# picoslidertoy.net
KiCad netlist of a schematic drawn in EAGLE
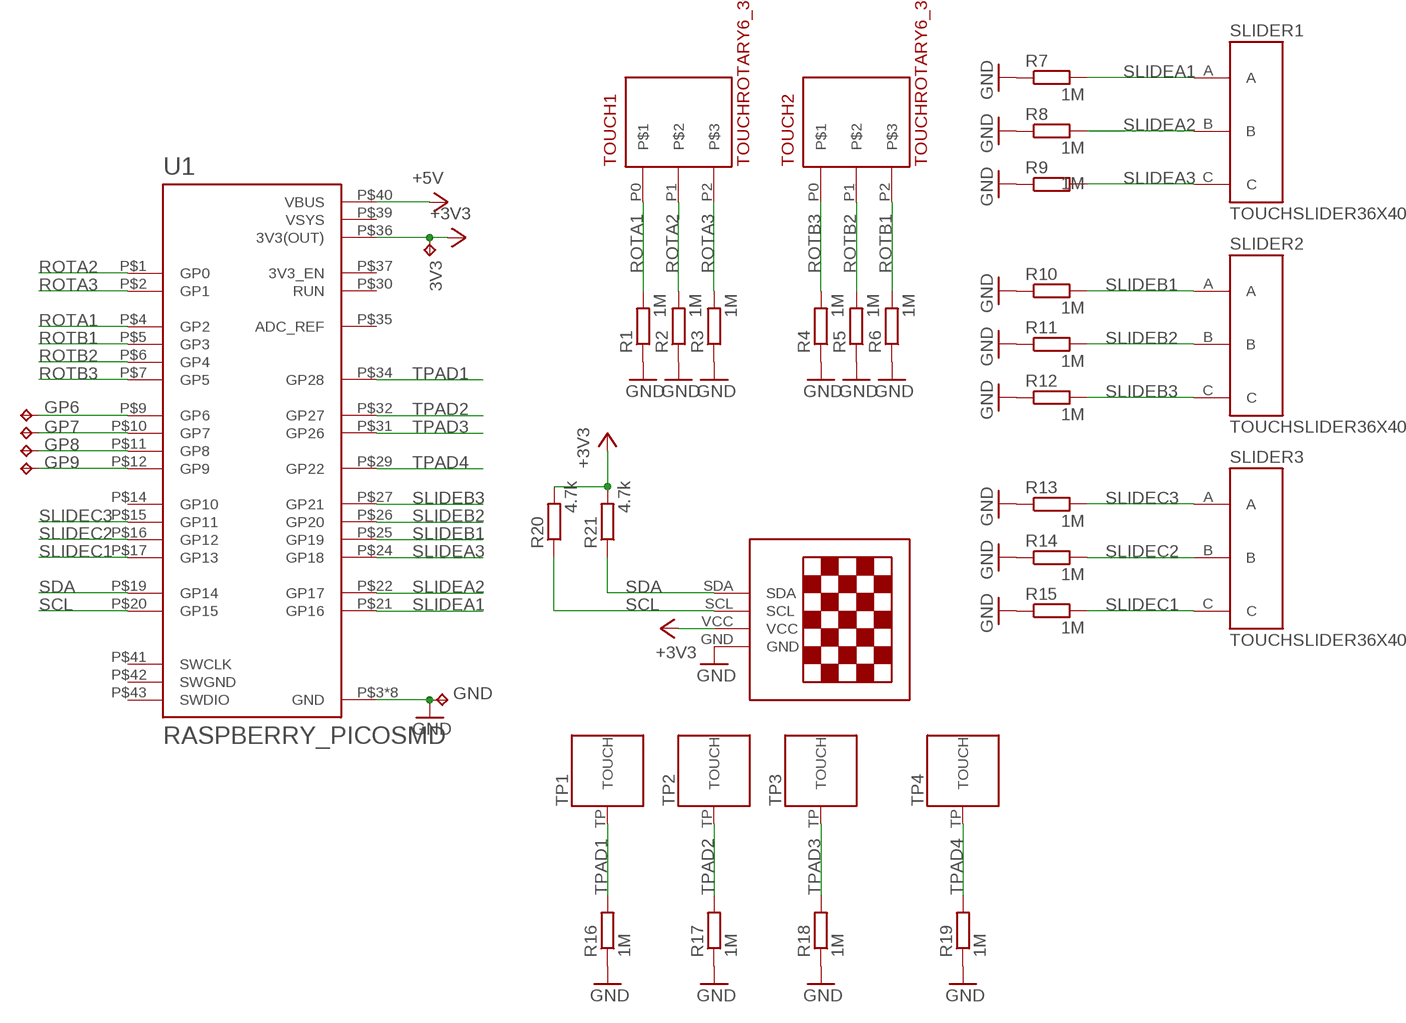
[diagram p0: schematic, sheet 1]

(export (version "E")
  (design (tool "Eeschema 10.0.6"))
  (components
    (comp (ref "3V3")
      (value "TPTP20R")
      (footprint "eagle-import:TP20R")
      (libsource (lib "eagle-import") (part "TPTP20R"))
    )
    (comp (ref "GND")
      (value "TPTP20R")
      (footprint "eagle-import:TP20R")
      (libsource (lib "eagle-import") (part "TPTP20R"))
    )
    (comp (ref "GP6")
      (value "TPTP20R")
      (footprint "eagle-import:TP20R")
      (libsource (lib "eagle-import") (part "TPTP20R"))
    )
    (comp (ref "GP7")
      (value "TPTP20R")
      (footprint "eagle-import:TP20R")
      (libsource (lib "eagle-import") (part "TPTP20R"))
    )
    (comp (ref "GP8")
      (value "TPTP20R")
      (footprint "eagle-import:TP20R")
      (libsource (lib "eagle-import") (part "TPTP20R"))
    )
    (comp (ref "GP9")
      (value "TPTP20R")
      (footprint "eagle-import:TP20R")
      (libsource (lib "eagle-import") (part "TPTP20R"))
    )
    (comp (ref "R1")
      (value "1M")
      (footprint "eagle-import:R0805")
      (libsource (lib "eagle-import") (part "R-EU_R0805"))
    )
    (comp (ref "R2")
      (value "1M")
      (footprint "eagle-import:R0805")
      (libsource (lib "eagle-import") (part "R-EU_R0805"))
    )
    (comp (ref "R3")
      (value "1M")
      (footprint "eagle-import:R0805")
      (libsource (lib "eagle-import") (part "R-EU_R0805"))
    )
    (comp (ref "R4")
      (value "1M")
      (footprint "eagle-import:R0805")
      (libsource (lib "eagle-import") (part "R-EU_R0805"))
    )
    (comp (ref "R5")
      (value "1M")
      (footprint "eagle-import:R0805")
      (libsource (lib "eagle-import") (part "R-EU_R0805"))
    )
    (comp (ref "R6")
      (value "1M")
      (footprint "eagle-import:R0805")
      (libsource (lib "eagle-import") (part "R-EU_R0805"))
    )
    (comp (ref "R7")
      (value "1M")
      (footprint "eagle-import:R0805")
      (libsource (lib "eagle-import") (part "R-EU_R0805"))
    )
    (comp (ref "R8")
      (value "1M")
      (footprint "eagle-import:R0805")
      (libsource (lib "eagle-import") (part "R-EU_R0805"))
    )
    (comp (ref "R9")
      (value "1M")
      (footprint "eagle-import:R0805")
      (libsource (lib "eagle-import") (part "R-EU_R0805"))
    )
    (comp (ref "R10")
      (value "1M")
      (footprint "eagle-import:R0805")
      (libsource (lib "eagle-import") (part "R-EU_R0805"))
    )
    (comp (ref "R11")
      (value "1M")
      (footprint "eagle-import:R0805")
      (libsource (lib "eagle-import") (part "R-EU_R0805"))
    )
    (comp (ref "R12")
      (value "1M")
      (footprint "eagle-import:R0805")
      (libsource (lib "eagle-import") (part "R-EU_R0805"))
    )
    (comp (ref "R13")
      (value "1M")
      (footprint "eagle-import:R0805")
      (libsource (lib "eagle-import") (part "R-EU_R0805"))
    )
    (comp (ref "R14")
      (value "1M")
      (footprint "eagle-import:R0805")
      (libsource (lib "eagle-import") (part "R-EU_R0805"))
    )
    (comp (ref "R15")
      (value "1M")
      (footprint "eagle-import:R0805")
      (libsource (lib "eagle-import") (part "R-EU_R0805"))
    )
    (comp (ref "R16")
      (value "1M")
      (footprint "eagle-import:R0805")
      (libsource (lib "eagle-import") (part "R-EU_R0805"))
    )
    (comp (ref "R17")
      (value "1M")
      (footprint "eagle-import:R0805")
      (libsource (lib "eagle-import") (part "R-EU_R0805"))
    )
    (comp (ref "R18")
      (value "1M")
      (footprint "eagle-import:R0805")
      (libsource (lib "eagle-import") (part "R-EU_R0805"))
    )
    (comp (ref "R19")
      (value "1M")
      (footprint "eagle-import:R0805")
      (libsource (lib "eagle-import") (part "R-EU_R0805"))
    )
    (comp (ref "R20")
      (value "4.7k")
      (footprint "eagle-import:R0805")
      (libsource (lib "eagle-import") (part "R-EU_R0805"))
    )
    (comp (ref "R21")
      (value "4.7k")
      (footprint "eagle-import:R0805")
      (libsource (lib "eagle-import") (part "R-EU_R0805"))
    )
    (comp (ref "SLIDER1")
      (value "TOUCHSLIDER36X40")
      (footprint "eagle-import:TOUCHSLIDER3_6X40")
      (libsource (lib "eagle-import") (part "TOUCHSLIDER36X40"))
    )
    (comp (ref "SLIDER2")
      (value "TOUCHSLIDER36X40")
      (footprint "eagle-import:TOUCHSLIDER3_6X40")
      (libsource (lib "eagle-import") (part "TOUCHSLIDER36X40"))
    )
    (comp (ref "SLIDER3")
      (value "TOUCHSLIDER36X40")
      (footprint "eagle-import:TOUCHSLIDER3_6X40")
      (libsource (lib "eagle-import") (part "TOUCHSLIDER36X40"))
    )
    (comp (ref "SMDBACK2")
      (value "13\"OLEDSMDONLY")
      (footprint "eagle-import:1.3_OLED_SMDBACKONLY")
      (libsource (lib "eagle-import") (part "13{dblquote}OLEDSMDONLY"))
    )
    (comp (ref "TOUCH1")
      (value "TOUCHROTARY6_30")
      (footprint "eagle-import:TOUCHROTARY1B")
      (libsource (lib "eagle-import") (part "TOUCHROTARY6_30"))
    )
    (comp (ref "TOUCH2")
      (value "TOUCHROTARY6_30")
      (footprint "eagle-import:TOUCHROTARY1B")
      (libsource (lib "eagle-import") (part "TOUCHROTARY6_30"))
    )
    (comp (ref "TP1")
      (value "TOUCHPADA")
      (footprint "eagle-import:TOUCHPADA_0.5IN")
      (libsource (lib "eagle-import") (part "TOUCHPADA"))
    )
    (comp (ref "TP2")
      (value "TOUCHPADA")
      (footprint "eagle-import:TOUCHPADA_0.5IN")
      (libsource (lib "eagle-import") (part "TOUCHPADA"))
    )
    (comp (ref "TP3")
      (value "TOUCHPADA")
      (footprint "eagle-import:TOUCHPADA_0.5IN")
      (libsource (lib "eagle-import") (part "TOUCHPADA"))
    )
    (comp (ref "TP4")
      (value "TOUCHPADA")
      (footprint "eagle-import:TOUCHPADA_0.5IN")
      (libsource (lib "eagle-import") (part "TOUCHPADA"))
    )
    (comp (ref "U1")
      (value "RASPBERRY_PICOSMD")
      (footprint "eagle-import:PICO-PKG-SMD")
      (libsource (lib "eagle-import") (part "RASPBERRY_PICOSMD"))
    )
  )
  (nets
    (net (code "1") (name "+3V3") (class "Default")
      (node (ref "3V3") (pin "TP") (pinfunction "TP_TP") (pintype "input"))
      (node (ref "R20") (pin "2") (pinfunction "2_2") (pintype "passive"))
      (node (ref "R21") (pin "2") (pinfunction "2_2") (pintype "passive"))
      (node (ref "SMDBACK2") (pin "VCC") (pinfunction "VCC_VCC") (pintype "bidirectional"))
      (node (ref "U1") (pin "P$36") (pinfunction "3V3(OUT)_P$36") (pintype "power_in"))
    )
    (net (code "2") (name "+5V") (class "Default")
      (node (ref "U1") (pin "P$40") (pinfunction "VBUS_P$40") (pintype "power_in"))
    )
    (net (code "3") (name "/ROTA1") (class "Default")
      (node (ref "R1") (pin "2") (pinfunction "2_2") (pintype "passive"))
      (node (ref "TOUCH1") (pin "P0") (pinfunction "P$1_P0") (pintype "bidirectional"))
      (node (ref "U1") (pin "P$4") (pinfunction "GP2_P$4") (pintype "bidirectional"))
    )
    (net (code "4") (name "/ROTA2") (class "Default")
      (node (ref "R2") (pin "2") (pinfunction "2_2") (pintype "passive"))
      (node (ref "TOUCH1") (pin "P1") (pinfunction "P$2_P1") (pintype "bidirectional"))
      (node (ref "U1") (pin "P$1") (pinfunction "GP0_P$1") (pintype "bidirectional"))
    )
    (net (code "5") (name "/ROTA3") (class "Default")
      (node (ref "R3") (pin "2") (pinfunction "2_2") (pintype "passive"))
      (node (ref "TOUCH1") (pin "P2") (pinfunction "P$3_P2") (pintype "bidirectional"))
      (node (ref "U1") (pin "P$2") (pinfunction "GP1_P$2") (pintype "bidirectional"))
    )
    (net (code "6") (name "/ROTB1") (class "Default")
      (node (ref "R6") (pin "2") (pinfunction "2_2") (pintype "passive"))
      (node (ref "TOUCH2") (pin "P2") (pinfunction "P$3_P2") (pintype "bidirectional"))
      (node (ref "U1") (pin "P$5") (pinfunction "GP3_P$5") (pintype "bidirectional"))
    )
    (net (code "7") (name "/ROTB2") (class "Default")
      (node (ref "R5") (pin "2") (pinfunction "2_2") (pintype "passive"))
      (node (ref "TOUCH2") (pin "P1") (pinfunction "P$2_P1") (pintype "bidirectional"))
      (node (ref "U1") (pin "P$6") (pinfunction "GP4_P$6") (pintype "bidirectional"))
    )
    (net (code "8") (name "/ROTB3") (class "Default")
      (node (ref "R4") (pin "2") (pinfunction "2_2") (pintype "passive"))
      (node (ref "TOUCH2") (pin "P0") (pinfunction "P$1_P0") (pintype "bidirectional"))
      (node (ref "U1") (pin "P$7") (pinfunction "GP5_P$7") (pintype "bidirectional"))
    )
    (net (code "9") (name "/SCL") (class "Default")
      (node (ref "R20") (pin "1") (pinfunction "1_1") (pintype "passive"))
      (node (ref "SMDBACK2") (pin "SCL") (pinfunction "SCL_SCL") (pintype "bidirectional"))
      (node (ref "U1") (pin "P$20") (pinfunction "GP15_P$20") (pintype "bidirectional"))
    )
    (net (code "10") (name "/SDA") (class "Default")
      (node (ref "R21") (pin "1") (pinfunction "1_1") (pintype "passive"))
      (node (ref "SMDBACK2") (pin "SDA") (pinfunction "SDA_SDA") (pintype "bidirectional"))
      (node (ref "U1") (pin "P$19") (pinfunction "GP14_P$19") (pintype "bidirectional"))
    )
    (net (code "11") (name "/SLIDEA1") (class "Default")
      (node (ref "R7") (pin "2") (pinfunction "2_2") (pintype "passive"))
      (node (ref "SLIDER1") (pin "A") (pinfunction "A_A") (pintype "bidirectional"))
      (node (ref "U1") (pin "P$21") (pinfunction "GP16_P$21") (pintype "bidirectional"))
    )
    (net (code "12") (name "/SLIDEA2") (class "Default")
      (node (ref "R8") (pin "2") (pinfunction "2_2") (pintype "passive"))
      (node (ref "SLIDER1") (pin "B") (pinfunction "B_B") (pintype "bidirectional"))
      (node (ref "U1") (pin "P$22") (pinfunction "GP17_P$22") (pintype "bidirectional"))
    )
    (net (code "13") (name "/SLIDEA3") (class "Default")
      (node (ref "R9") (pin "2") (pinfunction "2_2") (pintype "passive"))
      (node (ref "SLIDER1") (pin "C") (pinfunction "C_C") (pintype "bidirectional"))
      (node (ref "U1") (pin "P$24") (pinfunction "GP18_P$24") (pintype "bidirectional"))
    )
    (net (code "14") (name "/SLIDEB1") (class "Default")
      (node (ref "R10") (pin "2") (pinfunction "2_2") (pintype "passive"))
      (node (ref "SLIDER2") (pin "A") (pinfunction "A_A") (pintype "bidirectional"))
      (node (ref "U1") (pin "P$25") (pinfunction "GP19_P$25") (pintype "bidirectional"))
    )
    (net (code "15") (name "/SLIDEB2") (class "Default")
      (node (ref "R11") (pin "2") (pinfunction "2_2") (pintype "passive"))
      (node (ref "SLIDER2") (pin "B") (pinfunction "B_B") (pintype "bidirectional"))
      (node (ref "U1") (pin "P$26") (pinfunction "GP20_P$26") (pintype "bidirectional"))
    )
    (net (code "16") (name "/SLIDEB3") (class "Default")
      (node (ref "R12") (pin "2") (pinfunction "2_2") (pintype "passive"))
      (node (ref "SLIDER2") (pin "C") (pinfunction "C_C") (pintype "bidirectional"))
      (node (ref "U1") (pin "P$27") (pinfunction "GP21_P$27") (pintype "bidirectional"))
    )
    (net (code "17") (name "/SLIDEC1") (class "Default")
      (node (ref "R15") (pin "2") (pinfunction "2_2") (pintype "passive"))
      (node (ref "SLIDER3") (pin "C") (pinfunction "C_C") (pintype "bidirectional"))
      (node (ref "U1") (pin "P$17") (pinfunction "GP13_P$17") (pintype "bidirectional"))
    )
    (net (code "18") (name "/SLIDEC2") (class "Default")
      (node (ref "R14") (pin "2") (pinfunction "2_2") (pintype "passive"))
      (node (ref "SLIDER3") (pin "B") (pinfunction "B_B") (pintype "bidirectional"))
      (node (ref "U1") (pin "P$16") (pinfunction "GP12_P$16") (pintype "bidirectional"))
    )
    (net (code "19") (name "/SLIDEC3") (class "Default")
      (node (ref "R13") (pin "2") (pinfunction "2_2") (pintype "passive"))
      (node (ref "SLIDER3") (pin "A") (pinfunction "A_A") (pintype "bidirectional"))
      (node (ref "U1") (pin "P$15") (pinfunction "GP11_P$15") (pintype "bidirectional"))
    )
    (net (code "20") (name "/SWGND") (class "Default")
      (node (ref "U1") (pin "P$42") (pinfunction "SWGND_P$42") (pintype "power_in"))
    )
    (net (code "21") (name "/TPAD1") (class "Default")
      (node (ref "R16") (pin "2") (pinfunction "2_2") (pintype "passive"))
      (node (ref "TP1") (pin "TP") (pinfunction "TOUCH_TP") (pintype "bidirectional"))
      (node (ref "U1") (pin "P$34") (pinfunction "GP28_P$34") (pintype "bidirectional"))
    )
    (net (code "22") (name "/TPAD2") (class "Default")
      (node (ref "R17") (pin "2") (pinfunction "2_2") (pintype "passive"))
      (node (ref "TP2") (pin "TP") (pinfunction "TOUCH_TP") (pintype "bidirectional"))
      (node (ref "U1") (pin "P$32") (pinfunction "GP27_P$32") (pintype "bidirectional"))
    )
    (net (code "23") (name "/TPAD3") (class "Default")
      (node (ref "R18") (pin "2") (pinfunction "2_2") (pintype "passive"))
      (node (ref "TP3") (pin "TP") (pinfunction "TOUCH_TP") (pintype "bidirectional"))
      (node (ref "U1") (pin "P$31") (pinfunction "GP26_P$31") (pintype "bidirectional"))
    )
    (net (code "24") (name "/TPAD4") (class "Default")
      (node (ref "R19") (pin "2") (pinfunction "2_2") (pintype "passive"))
      (node (ref "TP4") (pin "TP") (pinfunction "TOUCH_TP") (pintype "bidirectional"))
      (node (ref "U1") (pin "P$29") (pinfunction "GP22_P$29") (pintype "bidirectional"))
    )
    (net (code "25") (name "/VSYS") (class "Default")
      (node (ref "U1") (pin "P$39") (pinfunction "VSYS_P$39") (pintype "power_in"))
    )
    (net (code "26") (name "GND") (class "Default")
      (node (ref "GND") (pin "TP") (pinfunction "TP_TP") (pintype "input"))
      (node (ref "R1") (pin "1") (pinfunction "1_1") (pintype "passive"))
      (node (ref "R10") (pin "1") (pinfunction "1_1") (pintype "passive"))
      (node (ref "R11") (pin "1") (pinfunction "1_1") (pintype "passive"))
      (node (ref "R12") (pin "1") (pinfunction "1_1") (pintype "passive"))
      (node (ref "R13") (pin "1") (pinfunction "1_1") (pintype "passive"))
      (node (ref "R14") (pin "1") (pinfunction "1_1") (pintype "passive"))
      (node (ref "R15") (pin "1") (pinfunction "1_1") (pintype "passive"))
      (node (ref "R16") (pin "1") (pinfunction "1_1") (pintype "passive"))
      (node (ref "R17") (pin "1") (pinfunction "1_1") (pintype "passive"))
      (node (ref "R18") (pin "1") (pinfunction "1_1") (pintype "passive"))
      (node (ref "R19") (pin "1") (pinfunction "1_1") (pintype "passive"))
      (node (ref "R2") (pin "1") (pinfunction "1_1") (pintype "passive"))
      (node (ref "R3") (pin "1") (pinfunction "1_1") (pintype "passive"))
      (node (ref "R4") (pin "1") (pinfunction "1_1") (pintype "passive"))
      (node (ref "R5") (pin "1") (pinfunction "1_1") (pintype "passive"))
      (node (ref "R6") (pin "1") (pinfunction "1_1") (pintype "passive"))
      (node (ref "R7") (pin "1") (pinfunction "1_1") (pintype "passive"))
      (node (ref "R8") (pin "1") (pinfunction "1_1") (pintype "passive"))
      (node (ref "R9") (pin "1") (pinfunction "1_1") (pintype "passive"))
      (node (ref "SMDBACK2") (pin "GND") (pinfunction "GND_GND") (pintype "bidirectional"))
      (node (ref "U1") (pin "P$13") (pinfunction "GND_P$13") (pintype "power_in"))
      (node (ref "U1") (pin "P$18") (pinfunction "GND_P$18") (pintype "power_in"))
      (node (ref "U1") (pin "P$23") (pinfunction "GND_P$23") (pintype "power_in"))
      (node (ref "U1") (pin "P$28") (pinfunction "GND_P$28") (pintype "power_in"))
      (node (ref "U1") (pin "P$3") (pinfunction "GND_P$3") (pintype "power_in"))
      (node (ref "U1") (pin "P$33") (pinfunction "GND_P$33") (pintype "power_in"))
      (node (ref "U1") (pin "P$38") (pinfunction "GND_P$38") (pintype "power_in"))
      (node (ref "U1") (pin "P$8") (pinfunction "GND_P$8") (pintype "power_in"))
    )
    (net (code "27") (name "Net-(U1-GP6)") (class "Default")
      (node (ref "GP6") (pin "TP") (pinfunction "TP_TP") (pintype "input"))
      (node (ref "U1") (pin "P$9") (pinfunction "GP6_P$9") (pintype "bidirectional"))
    )
    (net (code "28") (name "Net-(U1-GP7)") (class "Default")
      (node (ref "GP7") (pin "TP") (pinfunction "TP_TP") (pintype "input"))
      (node (ref "U1") (pin "P$10") (pinfunction "GP7_P$10") (pintype "bidirectional"))
    )
    (net (code "29") (name "Net-(U1-GP8)") (class "Default")
      (node (ref "GP8") (pin "TP") (pinfunction "TP_TP") (pintype "input"))
      (node (ref "U1") (pin "P$11") (pinfunction "GP8_P$11") (pintype "bidirectional"))
    )
    (net (code "30") (name "Net-(U1-GP9)") (class "Default")
      (node (ref "GP9") (pin "TP") (pinfunction "TP_TP") (pintype "input"))
      (node (ref "U1") (pin "P$12") (pinfunction "GP9_P$12") (pintype "bidirectional"))
    )
    (net (code "31") (name "unconnected-(U1-3V3_EN-PadP$37)") (class "Default")
      (node (ref "U1") (pin "P$37") (pinfunction "3V3_EN_P$37") (pintype "input"))
    )
    (net (code "32") (name "unconnected-(U1-ADC_REF-PadP$35)") (class "Default")
      (node (ref "U1") (pin "P$35") (pinfunction "ADC_REF_P$35") (pintype "input"))
    )
    (net (code "33") (name "unconnected-(U1-GP10-PadP$14)") (class "Default")
      (node (ref "U1") (pin "P$14") (pinfunction "GP10_P$14") (pintype "bidirectional"))
    )
    (net (code "34") (name "unconnected-(U1-RUN-PadP$30)") (class "Default")
      (node (ref "U1") (pin "P$30") (pinfunction "RUN_P$30") (pintype "input"))
    )
    (net (code "35") (name "unconnected-(U1-SWCLK-PadP$41)") (class "Default")
      (node (ref "U1") (pin "P$41") (pinfunction "SWCLK_P$41") (pintype "input"))
    )
    (net (code "36") (name "unconnected-(U1-SWDIO-PadP$43)") (class "Default")
      (node (ref "U1") (pin "P$43") (pinfunction "SWDIO_P$43") (pintype "bidirectional"))
    )
  )
)
